# SIM7020.net
KiCad netlist of a schematic drawn in Altium Designer
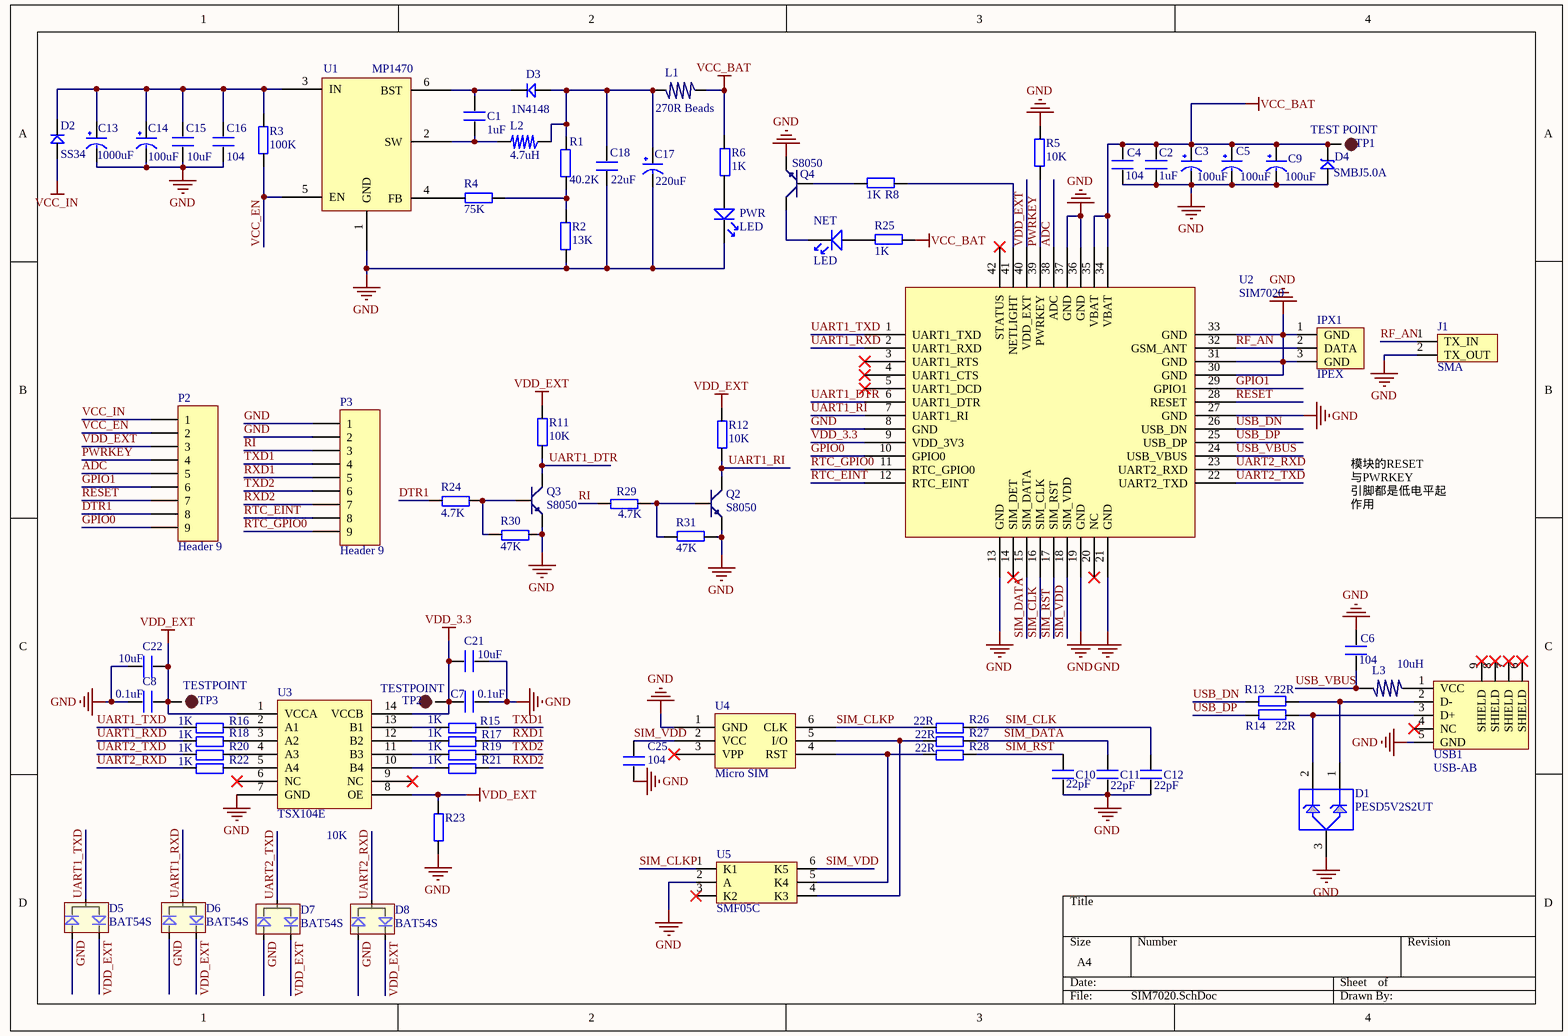
[diagram p0: SIM7020.SchDoc]

(export (version "E")
  (design (tool "Eeschema 10.0.6"))
  (components
    (comp (ref "C1") (value "1uF") (footprint "0603P") (libsource (lib "SIM7020") (part "C")))
    (comp (ref "C2") (value "1uF") (footprint "0603P") (libsource (lib "SIM7020") (part "C")))
    (comp (ref "C3") (value "100uF") (footprint "C3528") (libsource (lib "SIM7020") (part "CAP")))
    (comp (ref "C4") (value "104") (footprint "0603P") (libsource (lib "ALIENTEK_COMPONENT") (part "C")))
    (comp (ref "C5") (value "100uF") (footprint "C3528") (libsource (lib "SIM7020") (part "CAP")))
    (comp (ref "C6") (value "104") (footprint "0603P") (libsource (lib "ALIENTEK_COMPONENT") (part "C")))
    (comp (ref "C7") (value "0.1uF") (footprint "0603P") (libsource (lib "SIM7020") (part "C")))
    (comp (ref "C8") (value "0.1uF") (footprint "0603P") (libsource (lib "SIM7020") (part "C")))
    (comp (ref "C9") (value "100uF") (footprint "C3528") (libsource (lib "SIM7020") (part "CAP")))
    (comp (ref "C10") (value "22pF") (footprint "0402") (libsource (lib "ALIENTEK_COMPONENT") (part "C")))
    (comp (ref "C11") (value "22pF") (footprint "0402") (libsource (lib "ALIENTEK_COMPONENT") (part "C")))
    (comp (ref "C12") (value "22pF") (footprint "0402") (libsource (lib "ALIENTEK_COMPONENT") (part "C")))
    (comp (ref "C13")
      (value "1000uF")
      (footprint "CAP2.54")
      (libsource (lib "ALIENTEK_COMPONENT") (part "CAP"))
    )
    (comp (ref "C14") (value "100uF") (footprint "C3528") (libsource (lib "ALIENTEK_COMPONENT") (part "CAP")))
    (comp (ref "C15") (value "10uF") (footprint "0805") (libsource (lib "SIM7020") (part "C")))
    (comp (ref "C16") (value "104") (footprint "0603P") (libsource (lib "SIM7020") (part "C")))
    (comp (ref "C17") (value "220uF") (footprint "CC6.56.5") (libsource (lib "SIM7020") (part "CAP")))
    (comp (ref "C18") (value "22uF") (footprint "1206") (libsource (lib "SIM7020") (part "C")))
    (comp (ref "C21") (value "10uF") (footprint "0603P") (libsource (lib "SIM7020") (part "C")))
    (comp (ref "C22") (value "10uF") (footprint "0603P") (libsource (lib "SIM7020") (part "C")))
    (comp (ref "C25") (value "104") (footprint "0603P") (libsource (lib "ALIENTEK_COMPONENT") (part "C")))
    (comp (ref "D1")
      (value "PESD5V2S2UT")
      (footprint "SOT-23")
      (description "PESD5V2S2UT,SOT-23,NXP")
      (fields (field (name "Comment") "ESD-3"))
      (libsource (lib "02.MCU_KL25") (part "ESD-3"))
    )
    (comp (ref "D2")
      (value "SS34")
      (footprint "DIODE_3*5.3")
      (description "1N4148")
      (libsource (lib "alientek_sch_lib") (part "D"))
    )
    (comp (ref "D3") (value "1N4148") (footprint "DIODE_SOP") (libsource (lib "alientek_sch_lib") (part "D")))
    (comp (ref "D4")
      (value "SMBJ5.0A")
      (footprint "SMBJ")
      (description "TVS")
      (libsource (lib "ALIENTEK_COMPONENT") (part "SMBJ"))
    )
    (comp (ref "D5")
      (value "BAT54S")
      (footprint "SOT-23")
      (description "双肖特基二极管")
      (libsource (lib "ALIENTEK_COMPONENT") (part "BAT54S"))
    )
    (comp (ref "D6")
      (value "BAT54S")
      (footprint "SOT-23")
      (description "双肖特基二极管")
      (libsource (lib "ALIENTEK_COMPONENT") (part "BAT54S"))
    )
    (comp (ref "D7")
      (value "BAT54S")
      (footprint "SOT-23")
      (description "双肖特基二极管")
      (libsource (lib "ALIENTEK_COMPONENT") (part "BAT54S"))
    )
    (comp (ref "D8")
      (value "BAT54S")
      (footprint "SOT-23")
      (description "双肖特基二极管")
      (libsource (lib "ALIENTEK_COMPONENT") (part "BAT54S"))
    )
    (comp (ref "IPX1")
      (value "IPEX")
      (footprint "IPEX")
      (description "IPEX座")
      (libsource (lib "ATK_S1216F8_BD_V1.1") (part "IPEX"))
    )
    (comp (ref "J1")
      (value "SMA")
      (footprint "SMA-2")
      (description "SMA-2")
      (libsource (lib "SIM7020") (part "SMA-2"))
    )
    (comp (ref "L1") (value "270R Beads") (footprint "1206") (libsource (lib "SIM7020") (part "L")))
    (comp (ref "L2")
      (value "4.7uH")
      (footprint "L_CD43")
      (libsource (lib "ATK-7'TFTLCD电容触摸屏模块_V2.2") (part "L_SOP"))
    )
    (comp (ref "L3") (value "10uH") (footprint "0805") (libsource (lib "ALIENTEK_COMPONENT") (part "L")))
    (comp (ref "NET") (value "LED") (footprint "SMDLED") (libsource (lib "SIM7020") (part "LED")))
    (comp (ref "P2")
      (value "Header 9")
      (footprint "HDR1X9")
      (description "Header, 9-Pin")
      (fields (field (name "PUBLISHER") "Altium Limited"))
      (libsource (lib "Miscellaneous Connectors") (part "Header 9"))
    )
    (comp (ref "P3")
      (value "Header 9")
      (footprint "HDR1X9")
      (description "Header, 9-Pin")
      (fields (field (name "PUBLISHER") "Altium Limited"))
      (libsource (lib "Miscellaneous Connectors") (part "Header 9"))
    )
    (comp (ref "PWR") (value "LED") (footprint "SMDLED") (libsource (lib "SIM7020") (part "LED")))
    (comp (ref "Q2")
      (value "S8050")
      (footprint "SOT-23R")
      (description "8050/BCW846/BCW847")
      (libsource (lib "SIM7020") (part "NPN"))
    )
    (comp (ref "Q3")
      (value "S8050")
      (footprint "SOT-23R")
      (description "8050/BCW846/BCW847")
      (libsource (lib "SIM7020") (part "NPN"))
    )
    (comp (ref "Q4")
      (value "S8050")
      (footprint "SOT-23R")
      (description "8050/BCW846/BCW847")
      (libsource (lib "SIM7020") (part "NPN"))
    )
    (comp (ref "R1") (value "40.2K") (footprint "0603P") (libsource (lib "ALIENTEK_COMPONENT") (part "R")))
    (comp (ref "R2") (value "13K") (footprint "0603P") (libsource (lib "ALIENTEK_COMPONENT") (part "R")))
    (comp (ref "R3") (value "100K") (footprint "0603P") (libsource (lib "ALIENTEK_COMPONENT") (part "R")))
    (comp (ref "R4") (value "75K") (footprint "0603P") (libsource (lib "ALIENTEK_COMPONENT") (part "R")))
    (comp (ref "R5") (value "10K") (footprint "0603P") (libsource (lib "ALIENTEK_COMPONENT") (part "R")))
    (comp (ref "R6") (value "1K") (footprint "0603P") (libsource (lib "ALIENTEK_COMPONENT") (part "R")))
    (comp (ref "R8") (value "1K") (footprint "0603P") (libsource (lib "ALIENTEK_COMPONENT") (part "R")))
    (comp (ref "R11") (value "10K") (footprint "0603P") (libsource (lib "ALIENTEK_COMPONENT") (part "R")))
    (comp (ref "R12") (value "10K") (footprint "0603P") (libsource (lib "ALIENTEK_COMPONENT") (part "R")))
    (comp (ref "R13") (value "22R") (footprint "0603P") (libsource (lib "SIM7020") (part "R")))
    (comp (ref "R14") (value "22R") (footprint "0603P") (libsource (lib "SIM7020") (part "R")))
    (comp (ref "R15") (value "1K") (footprint "0603P") (libsource (lib "SIM7020") (part "R")))
    (comp (ref "R16") (value "1K") (footprint "0603P") (libsource (lib "SIM7020") (part "R")))
    (comp (ref "R17") (value "1K") (footprint "0603P") (libsource (lib "SIM7020") (part "R")))
    (comp (ref "R18") (value "1K") (footprint "0603P") (libsource (lib "SIM7020") (part "R")))
    (comp (ref "R19") (value "1K") (footprint "0603P") (libsource (lib "SIM7020") (part "R")))
    (comp (ref "R20") (value "1K") (footprint "0603P") (libsource (lib "SIM7020") (part "R")))
    (comp (ref "R21") (value "1K") (footprint "0603P") (libsource (lib "SIM7020") (part "R")))
    (comp (ref "R22") (value "1K") (footprint "0603P") (libsource (lib "SIM7020") (part "R")))
    (comp (ref "R23") (value "10K") (footprint "0603P") (libsource (lib "SIM7020") (part "R")))
    (comp (ref "R24") (value "4.7K") (footprint "0603P") (libsource (lib "ALIENTEK_COMPONENT") (part "R")))
    (comp (ref "R25") (value "1K") (footprint "0603P") (libsource (lib "ALIENTEK_COMPONENT") (part "R")))
    (comp (ref "R26") (value "22R") (footprint "0603P") (libsource (lib "SIM7020") (part "R")))
    (comp (ref "R27") (value "22R") (footprint "0603P") (libsource (lib "SIM7020") (part "R")))
    (comp (ref "R28") (value "22R") (footprint "0603P") (libsource (lib "SIM7020") (part "R")))
    (comp (ref "R29") (value "4.7K") (footprint "0603P") (libsource (lib "ALIENTEK_COMPONENT") (part "R")))
    (comp (ref "R30") (value "47K") (footprint "0603P") (libsource (lib "ALIENTEK_COMPONENT") (part "R")))
    (comp (ref "R31") (value "47K") (footprint "0603P") (libsource (lib "ALIENTEK_COMPONENT") (part "R")))
    (comp (ref "TP1")
      (value "TEST POINT")
      (footprint "TP-1.5")
      (description "测试点")
      (libsource (lib "ALIENTEK_COMPONENT") (part "TEST-POINT"))
    )
    (comp (ref "TP2")
      (value "TESTPOINT")
      (footprint "TP-1.5")
      (description "测试点")
      (libsource (lib "ALIENTEK_COMPONENT") (part "TEST-POINT"))
    )
    (comp (ref "TP3")
      (value "TESTPOINT")
      (footprint "TP-1.5")
      (description "测试点")
      (libsource (lib "ALIENTEK_COMPONENT") (part "TEST-POINT"))
    )
    (comp (ref "U1")
      (value "MP1470")
      (footprint "SOP23-6 - duplicate1")
      (libsource (lib "SIM7020") (part "MP1470"))
    )
    (comp (ref "U2")
      (value "SIM7020")
      (footprint "SIM7020")
      (description "NBloT")
      (libsource (lib "SIM7020") (part "SIM7020"))
    )
    (comp (ref "U3") (value "TSX104E") (footprint "TSX104E") (libsource (lib "SIM7020") (part "TSX104E")))
    (comp (ref "U4") (value "Micro SIM") (footprint "Micro SIM") (libsource (lib "plib") (part "Micro SIM")))
    (comp (ref "U5")
      (value "SMF05C")
      (footprint "SMF05C")
      (description "TVS")
      (libsource (lib "plib") (part "SMF05C"))
    )
    (comp (ref "USB1")
      (value "USB-AB")
      (footprint "USB_AB")
      (description "MicroUSB")
      (libsource (lib "ALIENTEK_COMPONENT") (part "USB-AB"))
    )
  )
  (nets
    (net (code "1") (name "/ADC") (class "Default")
      (node (ref "P2") (pin "5") (pinfunction "5_5") (pintype "passive"))
      (node (ref "U2") (pin "38") (pinfunction "ADC_38") (pintype "passive"))
    )
    (net (code "2") (name "/DTR1") (class "Default")
      (node (ref "P2") (pin "8") (pinfunction "8_8") (pintype "passive"))
      (node (ref "R24") (pin "1") (pintype "passive"))
    )
    (net (code "3") (name "/GPIO0") (class "Default")
      (node (ref "P2") (pin "9") (pinfunction "9_9") (pintype "passive"))
      (node (ref "U2") (pin "10") (pinfunction "GPIO0_10") (pintype "passive"))
    )
    (net (code "4") (name "/GPIO1") (class "Default")
      (node (ref "P2") (pin "6") (pinfunction "6_6") (pintype "passive"))
      (node (ref "U2") (pin "29") (pinfunction "GPIO1_29") (pintype "passive"))
    )
    (net (code "5") (name "/PWRKEY") (class "Default")
      (node (ref "P2") (pin "4") (pinfunction "4_4") (pintype "passive"))
      (node (ref "R5") (pin "2") (pintype "passive"))
      (node (ref "U2") (pin "39") (pinfunction "PWRKEY_39") (pintype "passive"))
    )
    (net (code "6") (name "/RESET") (class "Default")
      (node (ref "P2") (pin "7") (pinfunction "7_7") (pintype "passive"))
      (node (ref "U2") (pin "28") (pinfunction "RESET_28") (pintype "passive"))
    )
    (net (code "7") (name "/RF_AN") (class "Default")
      (node (ref "IPX1") (pin "2") (pinfunction "DATA_2") (pintype "passive"))
      (node (ref "J1") (pin "1") (pinfunction "TX_IN_1") (pintype "passive"))
      (node (ref "U2") (pin "32") (pinfunction "GSM_ANT_32") (pintype "passive"))
    )
    (net (code "8") (name "/RI") (class "Default")
      (node (ref "P3") (pin "3") (pinfunction "3_3") (pintype "passive"))
      (node (ref "R29") (pin "1") (pintype "passive"))
    )
    (net (code "9") (name "/RTC_EINT") (class "Default")
      (node (ref "P3") (pin "8") (pinfunction "8_8") (pintype "passive"))
      (node (ref "U2") (pin "12") (pinfunction "RTC_EINT_12") (pintype "passive"))
    )
    (net (code "10") (name "/RTC_GPIO0") (class "Default")
      (node (ref "P3") (pin "9") (pinfunction "9_9") (pintype "passive"))
      (node (ref "U2") (pin "11") (pinfunction "RTC_GPIO0_11") (pintype "passive"))
    )
    (net (code "11") (name "/RXD1") (class "Default")
      (node (ref "P3") (pin "5") (pinfunction "5_5") (pintype "passive"))
      (node (ref "R17") (pin "2") (pintype "passive"))
    )
    (net (code "12") (name "/RXD2") (class "Default")
      (node (ref "P3") (pin "7") (pinfunction "7_7") (pintype "passive"))
      (node (ref "R21") (pin "2") (pintype "passive"))
    )
    (net (code "13") (name "/SIM_CLK") (class "Default")
      (node (ref "C12") (pin "2") (pintype "passive"))
      (node (ref "R26") (pin "2") (pintype "passive"))
      (node (ref "U2") (pin "16") (pinfunction "SIM_CLK_16") (pintype "passive"))
    )
    (net (code "14") (name "/SIM_CLKP") (class "Default")
      (node (ref "R26") (pin "1") (pintype "passive"))
      (node (ref "U4") (pin "6") (pinfunction "CLK_6") (pintype "passive"))
      (node (ref "U5") (pin "1") (pinfunction "K1_1") (pintype "passive"))
    )
    (net (code "15") (name "/SIM_DATA") (class "Default")
      (node (ref "C11") (pin "2") (pintype "passive"))
      (node (ref "R27") (pin "2") (pintype "passive"))
      (node (ref "U2") (pin "15") (pinfunction "SIM_DATA_15") (pintype "passive"))
    )
    (net (code "16") (name "/SIM_RST") (class "Default")
      (node (ref "C10") (pin "1") (pintype "passive"))
      (node (ref "R28") (pin "2") (pintype "passive"))
      (node (ref "U2") (pin "17") (pinfunction "SIM_RST_17") (pintype "passive"))
    )
    (net (code "17") (name "/SIM_VDD") (class "Default")
      (node (ref "C25") (pin "2") (pintype "passive"))
      (node (ref "U2") (pin "18") (pinfunction "SIM_VDD_18") (pintype "passive"))
      (node (ref "U4") (pin "2") (pinfunction "VCC_2") (pintype "passive"))
      (node (ref "U5") (pin "6") (pinfunction "K5_6") (pintype "passive"))
    )
    (net (code "18") (name "/TXD1") (class "Default")
      (node (ref "P3") (pin "4") (pinfunction "4_4") (pintype "passive"))
      (node (ref "R15") (pin "2") (pintype "passive"))
    )
    (net (code "19") (name "/TXD2") (class "Default")
      (node (ref "P3") (pin "6") (pinfunction "6_6") (pintype "passive"))
      (node (ref "R19") (pin "2") (pintype "passive"))
    )
    (net (code "20") (name "/UART1_DTR") (class "Default")
      (node (ref "Q3") (pin "3") (pinfunction "C_3") (pintype "passive"))
      (node (ref "R11") (pin "1") (pintype "passive"))
      (node (ref "U2") (pin "6") (pinfunction "UART1_DTR_6") (pintype "passive"))
    )
    (net (code "21") (name "/UART1_RI") (class "Default")
      (node (ref "Q2") (pin "3") (pinfunction "C_3") (pintype "passive"))
      (node (ref "R12") (pin "1") (pintype "passive"))
      (node (ref "U2") (pin "7") (pinfunction "UART1_RI_7") (pintype "passive"))
    )
    (net (code "22") (name "/UART1_RXD") (class "Default")
      (node (ref "D6") (pin "3") (pintype "passive"))
      (node (ref "R18") (pin "1") (pintype "passive"))
      (node (ref "U2") (pin "2") (pinfunction "UART1_RXD_2") (pintype "passive"))
    )
    (net (code "23") (name "/UART1_TXD") (class "Default")
      (node (ref "D5") (pin "3") (pintype "passive"))
      (node (ref "R16") (pin "1") (pintype "passive"))
      (node (ref "U2") (pin "1") (pinfunction "UART1_TXD_1") (pintype "passive"))
    )
    (net (code "24") (name "/UART2_RXD") (class "Default")
      (node (ref "D8") (pin "3") (pintype "passive"))
      (node (ref "R22") (pin "1") (pintype "passive"))
      (node (ref "U2") (pin "23") (pinfunction "UART2_RXD_23") (pintype "passive"))
    )
    (net (code "25") (name "/UART2_TXD") (class "Default")
      (node (ref "D7") (pin "3") (pintype "passive"))
      (node (ref "R20") (pin "1") (pintype "passive"))
      (node (ref "U2") (pin "22") (pinfunction "UART2_TXD_22") (pintype "passive"))
    )
    (net (code "26") (name "/USB_DN") (class "Default")
      (node (ref "R13") (pin "2") (pintype "passive"))
      (node (ref "U2") (pin "26") (pinfunction "USB_DN_26") (pintype "passive"))
    )
    (net (code "27") (name "/USB_DP") (class "Default")
      (node (ref "R14") (pin "2") (pintype "passive"))
      (node (ref "U2") (pin "25") (pinfunction "USB_DP_25") (pintype "passive"))
    )
    (net (code "28") (name "/USB_VBUS") (class "Default")
      (node (ref "C6") (pin "1") (pintype "passive"))
      (node (ref "L3") (pin "2") (pintype "passive"))
      (node (ref "U2") (pin "24") (pinfunction "USB_VBUS_24") (pintype "passive"))
    )
    (net (code "29") (name "/VCC_EN") (class "Default")
      (node (ref "P2") (pin "2") (pinfunction "2_2") (pintype "passive"))
      (node (ref "R3") (pin "2") (pintype "passive"))
      (node (ref "U1") (pin "5") (pinfunction "EN_5") (pintype "passive"))
    )
    (net (code "30") (name "GND") (class "Default")
      (node (ref "C10") (pin "2") (pintype "passive"))
      (node (ref "C11") (pin "1") (pintype "passive"))
      (node (ref "C12") (pin "1") (pintype "passive"))
      (node (ref "C13") (pin "2") (pinfunction "GND_2") (pintype "passive"))
      (node (ref "C14") (pin "2") (pinfunction "GND_2") (pintype "passive"))
      (node (ref "C15") (pin "2") (pintype "passive"))
      (node (ref "C16") (pin "1") (pintype "passive"))
      (node (ref "C17") (pin "2") (pinfunction "GND_2") (pintype "passive"))
      (node (ref "C18") (pin "1") (pintype "passive"))
      (node (ref "C2") (pin "1") (pintype "passive"))
      (node (ref "C21") (pin "2") (pintype "passive"))
      (node (ref "C22") (pin "1") (pintype "passive"))
      (node (ref "C25") (pin "1") (pintype "passive"))
      (node (ref "C3") (pin "2") (pinfunction "GND_2") (pintype "passive"))
      (node (ref "C4") (pin "1") (pintype "passive"))
      (node (ref "C5") (pin "2") (pinfunction "GND_2") (pintype "passive"))
      (node (ref "C6") (pin "2") (pintype "passive"))
      (node (ref "C7") (pin "2") (pintype "passive"))
      (node (ref "C8") (pin "2") (pintype "passive"))
      (node (ref "C9") (pin "2") (pinfunction "GND_2") (pintype "passive"))
      (node (ref "D1") (pin "3") (pinfunction "3_3") (pintype "passive"))
      (node (ref "D4") (pin "1") (pintype "passive"))
      (node (ref "D5") (pin "1") (pintype "passive"))
      (node (ref "D6") (pin "1") (pintype "passive"))
      (node (ref "D7") (pin "1") (pintype "passive"))
      (node (ref "D8") (pin "1") (pintype "passive"))
      (node (ref "IPX1") (pin "1") (pinfunction "GND_1") (pintype "passive"))
      (node (ref "IPX1") (pin "3") (pinfunction "GND_3") (pintype "passive"))
      (node (ref "J1") (pin "2") (pinfunction "TX_OUT_2") (pintype "passive"))
      (node (ref "P3") (pin "1") (pinfunction "1_1") (pintype "passive"))
      (node (ref "P3") (pin "2") (pinfunction "2_2") (pintype "passive"))
      (node (ref "PWR") (pin "2") (pinfunction "2_2") (pintype "passive"))
      (node (ref "Q2") (pin "1") (pinfunction "E_1") (pintype "passive"))
      (node (ref "Q3") (pin "1") (pinfunction "E_1") (pintype "passive"))
      (node (ref "Q4") (pin "1") (pinfunction "E_1") (pintype "passive"))
      (node (ref "R2") (pin "2") (pintype "passive"))
      (node (ref "R23") (pin "1") (pintype "passive"))
      (node (ref "R30") (pin "2") (pintype "passive"))
      (node (ref "R31") (pin "1") (pintype "passive"))
      (node (ref "R5") (pin "1") (pintype "passive"))
      (node (ref "U1") (pin "1") (pinfunction "GND_1") (pintype "passive"))
      (node (ref "U2") (pin "13") (pinfunction "GND_13") (pintype "passive"))
      (node (ref "U2") (pin "19") (pinfunction "GND_19") (pintype "passive"))
      (node (ref "U2") (pin "21") (pinfunction "GND_21") (pintype "passive"))
      (node (ref "U2") (pin "27") (pinfunction "GND_27") (pintype "passive"))
      (node (ref "U2") (pin "30") (pinfunction "GND_30") (pintype "passive"))
      (node (ref "U2") (pin "31") (pinfunction "GND_31") (pintype "passive"))
      (node (ref "U2") (pin "33") (pinfunction "GND_33") (pintype "passive"))
      (node (ref "U2") (pin "36") (pinfunction "GND_36") (pintype "passive"))
      (node (ref "U2") (pin "37") (pinfunction "GND_37") (pintype "passive"))
      (node (ref "U2") (pin "8") (pinfunction "GND_8") (pintype "passive"))
      (node (ref "U3") (pin "7") (pinfunction "GND_7") (pintype "passive"))
      (node (ref "U4") (pin "1") (pinfunction "GND_1") (pintype "passive"))
      (node (ref "U5") (pin "2") (pinfunction "A_2") (pintype "passive"))
      (node (ref "USB1") (pin "5") (pinfunction "GND_5") (pintype "passive"))
    )
    (net (code "31") (name "Net-(C13-VCC)") (class "Default")
      (node (ref "C13") (pin "1") (pinfunction "VCC_1") (pintype "passive"))
      (node (ref "C14") (pin "1") (pinfunction "VCC_1") (pintype "passive"))
      (node (ref "C15") (pin "1") (pintype "passive"))
      (node (ref "C16") (pin "2") (pintype "passive"))
      (node (ref "D2") (pin "2") (pintype "passive"))
      (node (ref "R3") (pin "1") (pintype "passive"))
      (node (ref "U1") (pin "3") (pinfunction "IN_3") (pintype "passive"))
    )
    (net (code "32") (name "Net-(C17-VCC)") (class "Default")
      (node (ref "C17") (pin "1") (pinfunction "VCC_1") (pintype "passive"))
      (node (ref "C18") (pin "2") (pintype "passive"))
      (node (ref "D3") (pin "1") (pintype "passive"))
      (node (ref "L1") (pin "2") (pintype "passive"))
      (node (ref "L2") (pin "1") (pinfunction "1_1") (pintype "passive"))
      (node (ref "R1") (pin "1") (pintype "passive"))
    )
    (net (code "33") (name "Net-(NET-Pad1)") (class "Default")
      (node (ref "NET") (pin "1") (pinfunction "1_1") (pintype "passive"))
      (node (ref "R25") (pin "2") (pintype "passive"))
    )
    (net (code "34") (name "Net-(PWR-Pad1)") (class "Default")
      (node (ref "PWR") (pin "1") (pinfunction "1_1") (pintype "passive"))
      (node (ref "R6") (pin "1") (pintype "passive"))
    )
    (net (code "35") (name "Net-(Q2-B)") (class "Default")
      (node (ref "Q2") (pin "2") (pinfunction "B_2") (pintype "passive"))
      (node (ref "R29") (pin "2") (pintype "passive"))
      (node (ref "R31") (pin "2") (pintype "passive"))
    )
    (net (code "36") (name "Net-(Q3-B)") (class "Default")
      (node (ref "Q3") (pin "2") (pinfunction "B_2") (pintype "passive"))
      (node (ref "R24") (pin "2") (pintype "passive"))
      (node (ref "R30") (pin "1") (pintype "passive"))
    )
    (net (code "37") (name "Net-(Q4-B)") (class "Default")
      (node (ref "Q4") (pin "2") (pinfunction "B_2") (pintype "passive"))
      (node (ref "R8") (pin "2") (pintype "passive"))
    )
    (net (code "38") (name "Net-(Q4-C)") (class "Default")
      (node (ref "NET") (pin "2") (pinfunction "2_2") (pintype "passive"))
      (node (ref "Q4") (pin "3") (pinfunction "C_3") (pintype "passive"))
    )
    (net (code "39") (name "Net-(R1-Pad2)") (class "Default")
      (node (ref "R1") (pin "2") (pintype "passive"))
      (node (ref "R2") (pin "1") (pintype "passive"))
      (node (ref "R4") (pin "1") (pintype "passive"))
    )
    (net (code "40") (name "Net-(U1-BST)") (class "Default")
      (node (ref "C1") (pin "1") (pintype "passive"))
      (node (ref "D3") (pin "2") (pintype "passive"))
      (node (ref "U1") (pin "6") (pinfunction "BST_6") (pintype "passive"))
    )
    (net (code "41") (name "Net-(U1-FB)") (class "Default")
      (node (ref "R4") (pin "2") (pintype "passive"))
      (node (ref "U1") (pin "4") (pinfunction "FB_4") (pintype "passive"))
    )
    (net (code "42") (name "Net-(U1-SW)") (class "Default")
      (node (ref "C1") (pin "2") (pintype "passive"))
      (node (ref "L2") (pin "2") (pinfunction "2_2") (pintype "passive"))
      (node (ref "U1") (pin "2") (pinfunction "SW_2") (pintype "passive"))
    )
    (net (code "43") (name "Net-(U2-NETLIGHT)") (class "Default")
      (node (ref "R8") (pin "1") (pintype "passive"))
      (node (ref "U2") (pin "41") (pinfunction "NETLIGHT_41") (pintype "passive"))
    )
    (net (code "44") (name "Net-(U3-A1)") (class "Default")
      (node (ref "R16") (pin "2") (pintype "passive"))
      (node (ref "U3") (pin "2") (pinfunction "A1_2") (pintype "passive"))
    )
    (net (code "45") (name "Net-(U3-A2)") (class "Default")
      (node (ref "R18") (pin "2") (pintype "passive"))
      (node (ref "U3") (pin "3") (pinfunction "A2_3") (pintype "passive"))
    )
    (net (code "46") (name "Net-(U3-A3)") (class "Default")
      (node (ref "R20") (pin "2") (pintype "passive"))
      (node (ref "U3") (pin "4") (pinfunction "A3_4") (pintype "passive"))
    )
    (net (code "47") (name "Net-(U3-A4)") (class "Default")
      (node (ref "R22") (pin "2") (pintype "passive"))
      (node (ref "U3") (pin "5") (pinfunction "A4_5") (pintype "passive"))
    )
    (net (code "48") (name "Net-(U3-B1)") (class "Default")
      (node (ref "R15") (pin "1") (pintype "passive"))
      (node (ref "U3") (pin "13") (pinfunction "B1_13") (pintype "passive"))
    )
    (net (code "49") (name "Net-(U3-B2)") (class "Default")
      (node (ref "R17") (pin "1") (pintype "passive"))
      (node (ref "U3") (pin "12") (pinfunction "B2_12") (pintype "passive"))
    )
    (net (code "50") (name "Net-(U3-B3)") (class "Default")
      (node (ref "R19") (pin "1") (pintype "passive"))
      (node (ref "U3") (pin "11") (pinfunction "B3_11") (pintype "passive"))
    )
    (net (code "51") (name "Net-(U3-B4)") (class "Default")
      (node (ref "R21") (pin "1") (pintype "passive"))
      (node (ref "U3") (pin "10") (pinfunction "B4_10") (pintype "passive"))
    )
    (net (code "52") (name "Net-(U4-I{slash}O)") (class "Default")
      (node (ref "R27") (pin "1") (pintype "passive"))
      (node (ref "U4") (pin "5") (pinfunction "I/O_5") (pintype "passive"))
      (node (ref "U5") (pin "4") (pinfunction "K3_4") (pintype "passive"))
    )
    (net (code "53") (name "Net-(U4-RST)") (class "Default")
      (node (ref "R28") (pin "1") (pintype "passive"))
      (node (ref "U4") (pin "4") (pinfunction "RST_4") (pintype "passive"))
      (node (ref "U5") (pin "5") (pinfunction "K4_5") (pintype "passive"))
    )
    (net (code "54") (name "Net-(USB1-D+)") (class "Default")
      (node (ref "D1") (pin "2") (pinfunction "2_2") (pintype "passive"))
      (node (ref "R14") (pin "1") (pintype "passive"))
      (node (ref "USB1") (pin "3") (pinfunction "D+_3") (pintype "passive"))
    )
    (net (code "55") (name "Net-(USB1-D-)") (class "Default")
      (node (ref "D1") (pin "1") (pinfunction "1_1") (pintype "passive"))
      (node (ref "R13") (pin "1") (pintype "passive"))
      (node (ref "USB1") (pin "2") (pinfunction "D-_2") (pintype "passive"))
    )
    (net (code "56") (name "Net-(USB1-VCC)") (class "Default")
      (node (ref "L3") (pin "1") (pintype "passive"))
      (node (ref "USB1") (pin "1") (pinfunction "VCC_1") (pintype "passive"))
    )
    (net (code "57") (name "VCC_BAT") (class "Default")
      (node (ref "C2") (pin "2") (pintype "passive"))
      (node (ref "C3") (pin "1") (pinfunction "VCC_1") (pintype "passive"))
      (node (ref "C4") (pin "2") (pintype "passive"))
      (node (ref "C5") (pin "1") (pinfunction "VCC_1") (pintype "passive"))
      (node (ref "C9") (pin "1") (pinfunction "VCC_1") (pintype "passive"))
      (node (ref "D4") (pin "2") (pintype "passive"))
      (node (ref "L1") (pin "1") (pintype "passive"))
      (node (ref "R25") (pin "1") (pintype "passive"))
      (node (ref "R6") (pin "2") (pintype "passive"))
      (node (ref "TP1") (pin "1") (pinfunction "1_1") (pintype "passive"))
      (node (ref "U2") (pin "34") (pinfunction "VBAT_34") (pintype "passive"))
      (node (ref "U2") (pin "35") (pinfunction "VBAT_35") (pintype "passive"))
    )
    (net (code "58") (name "VCC_IN") (class "Default")
      (node (ref "D2") (pin "1") (pintype "passive"))
      (node (ref "P2") (pin "1") (pinfunction "1_1") (pintype "passive"))
    )
    (net (code "59") (name "VDD_3.3") (class "Default")
      (node (ref "C21") (pin "1") (pintype "passive"))
      (node (ref "C7") (pin "1") (pintype "passive"))
      (node (ref "TP2") (pin "1") (pinfunction "1_1") (pintype "passive"))
      (node (ref "U2") (pin "9") (pinfunction "VDD_3V3_9") (pintype "passive"))
      (node (ref "U3") (pin "14") (pinfunction "VCCB_14") (pintype "passive"))
    )
    (net (code "60") (name "VDD_EXT") (class "Default")
      (node (ref "C22") (pin "2") (pintype "passive"))
      (node (ref "C8") (pin "1") (pintype "passive"))
      (node (ref "D5") (pin "2") (pintype "passive"))
      (node (ref "D6") (pin "2") (pintype "passive"))
      (node (ref "D7") (pin "2") (pintype "passive"))
      (node (ref "D8") (pin "2") (pintype "passive"))
      (node (ref "P2") (pin "3") (pinfunction "3_3") (pintype "passive"))
      (node (ref "R11") (pin "2") (pintype "passive"))
      (node (ref "R12") (pin "2") (pintype "passive"))
      (node (ref "R23") (pin "2") (pintype "passive"))
      (node (ref "TP3") (pin "1") (pinfunction "1_1") (pintype "passive"))
      (node (ref "U2") (pin "40") (pinfunction "VDD_EXT_40") (pintype "passive"))
      (node (ref "U3") (pin "1") (pinfunction "VCCA_1") (pintype "passive"))
      (node (ref "U3") (pin "8") (pinfunction "OE_8") (pintype "passive"))
    )
    (net (code "61") (name "unconnected-(U2-NC-Pad20)") (class "Default")
      (node (ref "U2") (pin "20") (pinfunction "NC_20") (pintype "passive+no_connect"))
    )
    (net (code "62") (name "unconnected-(U2-SIM_DET-Pad14)") (class "Default")
      (node (ref "U2") (pin "14") (pinfunction "SIM_DET_14") (pintype "passive+no_connect"))
    )
    (net (code "63") (name "unconnected-(U2-STATUS-Pad42)") (class "Default")
      (node (ref "U2") (pin "42") (pinfunction "STATUS_42") (pintype "passive+no_connect"))
    )
    (net (code "64") (name "unconnected-(U2-UART1_CTS-Pad4)") (class "Default")
      (node (ref "U2") (pin "4") (pinfunction "UART1_CTS_4") (pintype "passive+no_connect"))
    )
    (net (code "65") (name "unconnected-(U2-UART1_DCD-Pad5)") (class "Default")
      (node (ref "U2") (pin "5") (pinfunction "UART1_DCD_5") (pintype "passive+no_connect"))
    )
    (net (code "66") (name "unconnected-(U2-UART1_RTS-Pad3)") (class "Default")
      (node (ref "U2") (pin "3") (pinfunction "UART1_RTS_3") (pintype "passive+no_connect"))
    )
    (net (code "67") (name "unconnected-(U3-NC-Pad6)") (class "Default")
      (node (ref "U3") (pin "6") (pinfunction "NC_6") (pintype "passive+no_connect"))
    )
    (net (code "68") (name "unconnected-(U3-NC-Pad9)") (class "Default")
      (node (ref "U3") (pin "9") (pinfunction "NC_9") (pintype "passive+no_connect"))
    )
    (net (code "69") (name "unconnected-(U4-VPP-Pad3)") (class "Default")
      (node (ref "U4") (pin "3") (pinfunction "VPP_3") (pintype "passive+no_connect"))
    )
    (net (code "70") (name "unconnected-(U5-K2-Pad3)") (class "Default")
      (node (ref "U5") (pin "3") (pinfunction "K2_3") (pintype "passive+no_connect"))
    )
    (net (code "71") (name "unconnected-(USB1-NC-Pad4)") (class "Default")
      (node (ref "USB1") (pin "4") (pinfunction "NC_4") (pintype "passive+no_connect"))
    )
    (net (code "72") (name "unconnected-(USB1-SHIELD-Pad6)") (class "Default")
      (node (ref "USB1") (pin "6") (pinfunction "SHIELD_6") (pintype "passive+no_connect"))
    )
    (net (code "73") (name "unconnected-(USB1-SHIELD-Pad7)") (class "Default")
      (node (ref "USB1") (pin "7") (pinfunction "SHIELD_7") (pintype "passive+no_connect"))
    )
    (net (code "74") (name "unconnected-(USB1-SHIELD-Pad8)") (class "Default")
      (node (ref "USB1") (pin "8") (pinfunction "SHIELD_8") (pintype "passive+no_connect"))
    )
    (net (code "75") (name "unconnected-(USB1-SHIELD-Pad9)") (class "Default")
      (node (ref "USB1") (pin "9") (pinfunction "SHIELD_9") (pintype "passive+no_connect"))
    )
  )
)
